# Dual_LM317.net
KiCad netlist of a schematic drawn in EAGLE
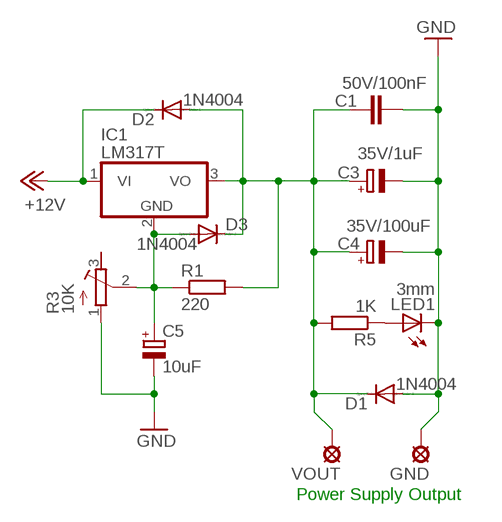
[diagram p0: schematic, sheet 1]

(export (version "E")
  (design (tool "Eeschema 10.0.6"))
  (components
    (comp (ref "C1")
      (value "50V/100nF")
      (footprint "eagle-import:C2.5-2")
      (libsource (lib "eagle-import") (part "C2.5/2"))
    )
    (comp (ref "C3")
      (value "35V/1uF")
      (footprint "eagle-import:E2-5")
      (libsource (lib "eagle-import") (part "CPOL-EUE2-5"))
    )
    (comp (ref "C4")
      (value "35V/100uF")
      (footprint "eagle-import:E2-5")
      (libsource (lib "eagle-import") (part "CPOL-EUE2-5"))
    )
    (comp (ref "C5")
      (value "10uF")
      (footprint "eagle-import:E2-5")
      (libsource (lib "eagle-import") (part "CPOL-EUE2-5"))
    )
    (comp (ref "D1")
      (value "1N4004")
      (footprint "eagle-import:DO41-10")
      (libsource (lib "eagle-import") (part "1N4004"))
    )
    (comp (ref "D2")
      (value "1N4004")
      (footprint "eagle-import:DO41-10")
      (libsource (lib "eagle-import") (part "1N4004"))
    )
    (comp (ref "D3")
      (value "1N4004")
      (footprint "eagle-import:DO41-10")
      (libsource (lib "eagle-import") (part "1N4004"))
    )
    (comp (ref "GND")
      (value "SE14")
      (footprint "eagle-import:SE14")
      (libsource (lib "eagle-import") (part "SE14"))
    )
    (comp (ref "IC1")
      (value "LM317T")
      (footprint "eagle-import:TO220V")
      (libsource (lib "eagle-import") (part "78TV12"))
    )
    (comp (ref "LED1")
      (value "3mm")
      (footprint "eagle-import:LED3MM")
      (libsource (lib "eagle-import") (part "LED3MM"))
    )
    (comp (ref "R1")
      (value "220")
      (footprint "eagle-import:0204_5")
      (libsource (lib "eagle-import") (part "R-EU_0204/5"))
    )
    (comp (ref "R3")
      (value "10K")
      (footprint "eagle-import:RTRIM64Y")
      (libsource (lib "eagle-import") (part "R-TRIMM64Y"))
    )
    (comp (ref "R5")
      (value "1K")
      (footprint "eagle-import:0204_5")
      (libsource (lib "eagle-import") (part "R-EU_0204/5"))
    )
    (comp (ref "VOUT")
      (value "SE14")
      (footprint "eagle-import:SE14")
      (libsource (lib "eagle-import") (part "SE14"))
    )
  )
  (nets
    (net (code "1") (name "+12V") (class "Default")
      (node (ref "D2") (pin "C") (pinfunction "C_C") (pintype "passive"))
      (node (ref "IC1") (pin "1") (pinfunction "VI_1") (pintype "input"))
    )
    (net (code "2") (name "GND") (class "Default")
      (node (ref "C1") (pin "2") (pinfunction "2_2") (pintype "passive"))
      (node (ref "C3") (pin "-") (pinfunction "-_-") (pintype "passive"))
      (node (ref "C4") (pin "-") (pinfunction "-_-") (pintype "passive"))
      (node (ref "C5") (pin "-") (pinfunction "-_-") (pintype "passive"))
      (node (ref "D1") (pin "A") (pinfunction "A_A") (pintype "passive"))
      (node (ref "GND") (pin "MP") (pinfunction "MP_MP") (pintype "passive"))
      (node (ref "LED1") (pin "K") (pinfunction "C_K") (pintype "passive"))
      (node (ref "R3") (pin "1") (pinfunction "A_1") (pintype "passive"))
    )
    (net (code "3") (name "Net-(IC1-GND)") (class "Default")
      (node (ref "C5") (pin "+") (pinfunction "+_+") (pintype "passive"))
      (node (ref "D3") (pin "A") (pinfunction "A_A") (pintype "passive"))
      (node (ref "IC1") (pin "2") (pinfunction "GND_2") (pintype "passive"))
      (node (ref "R1") (pin "1") (pinfunction "1_1") (pintype "passive"))
      (node (ref "R3") (pin "2") (pinfunction "S_2") (pintype "passive"))
    )
    (net (code "4") (name "Net-(IC1-VO)") (class "Default")
      (node (ref "C1") (pin "1") (pinfunction "1_1") (pintype "passive"))
      (node (ref "C3") (pin "+") (pinfunction "+_+") (pintype "passive"))
      (node (ref "C4") (pin "+") (pinfunction "+_+") (pintype "passive"))
      (node (ref "D1") (pin "C") (pinfunction "C_C") (pintype "passive"))
      (node (ref "D2") (pin "A") (pinfunction "A_A") (pintype "passive"))
      (node (ref "D3") (pin "C") (pinfunction "C_C") (pintype "passive"))
      (node (ref "IC1") (pin "3") (pinfunction "VO_3") (pintype "passive"))
      (node (ref "R1") (pin "2") (pinfunction "2_2") (pintype "passive"))
      (node (ref "R5") (pin "2") (pinfunction "2_2") (pintype "passive"))
      (node (ref "VOUT") (pin "MP") (pinfunction "MP_MP") (pintype "passive"))
    )
    (net (code "5") (name "Net-(LED1-PadA)") (class "Default")
      (node (ref "LED1") (pin "A") (pinfunction "A_A") (pintype "passive"))
      (node (ref "R5") (pin "1") (pinfunction "1_1") (pintype "passive"))
    )
    (net (code "6") (name "unconnected-(R3-E-Pad3)") (class "Default")
      (node (ref "R3") (pin "3") (pinfunction "E_3") (pintype "passive"))
    )
  )
)
